# p2-001.net
KiCad netlist of a schematic drawn in EAGLE
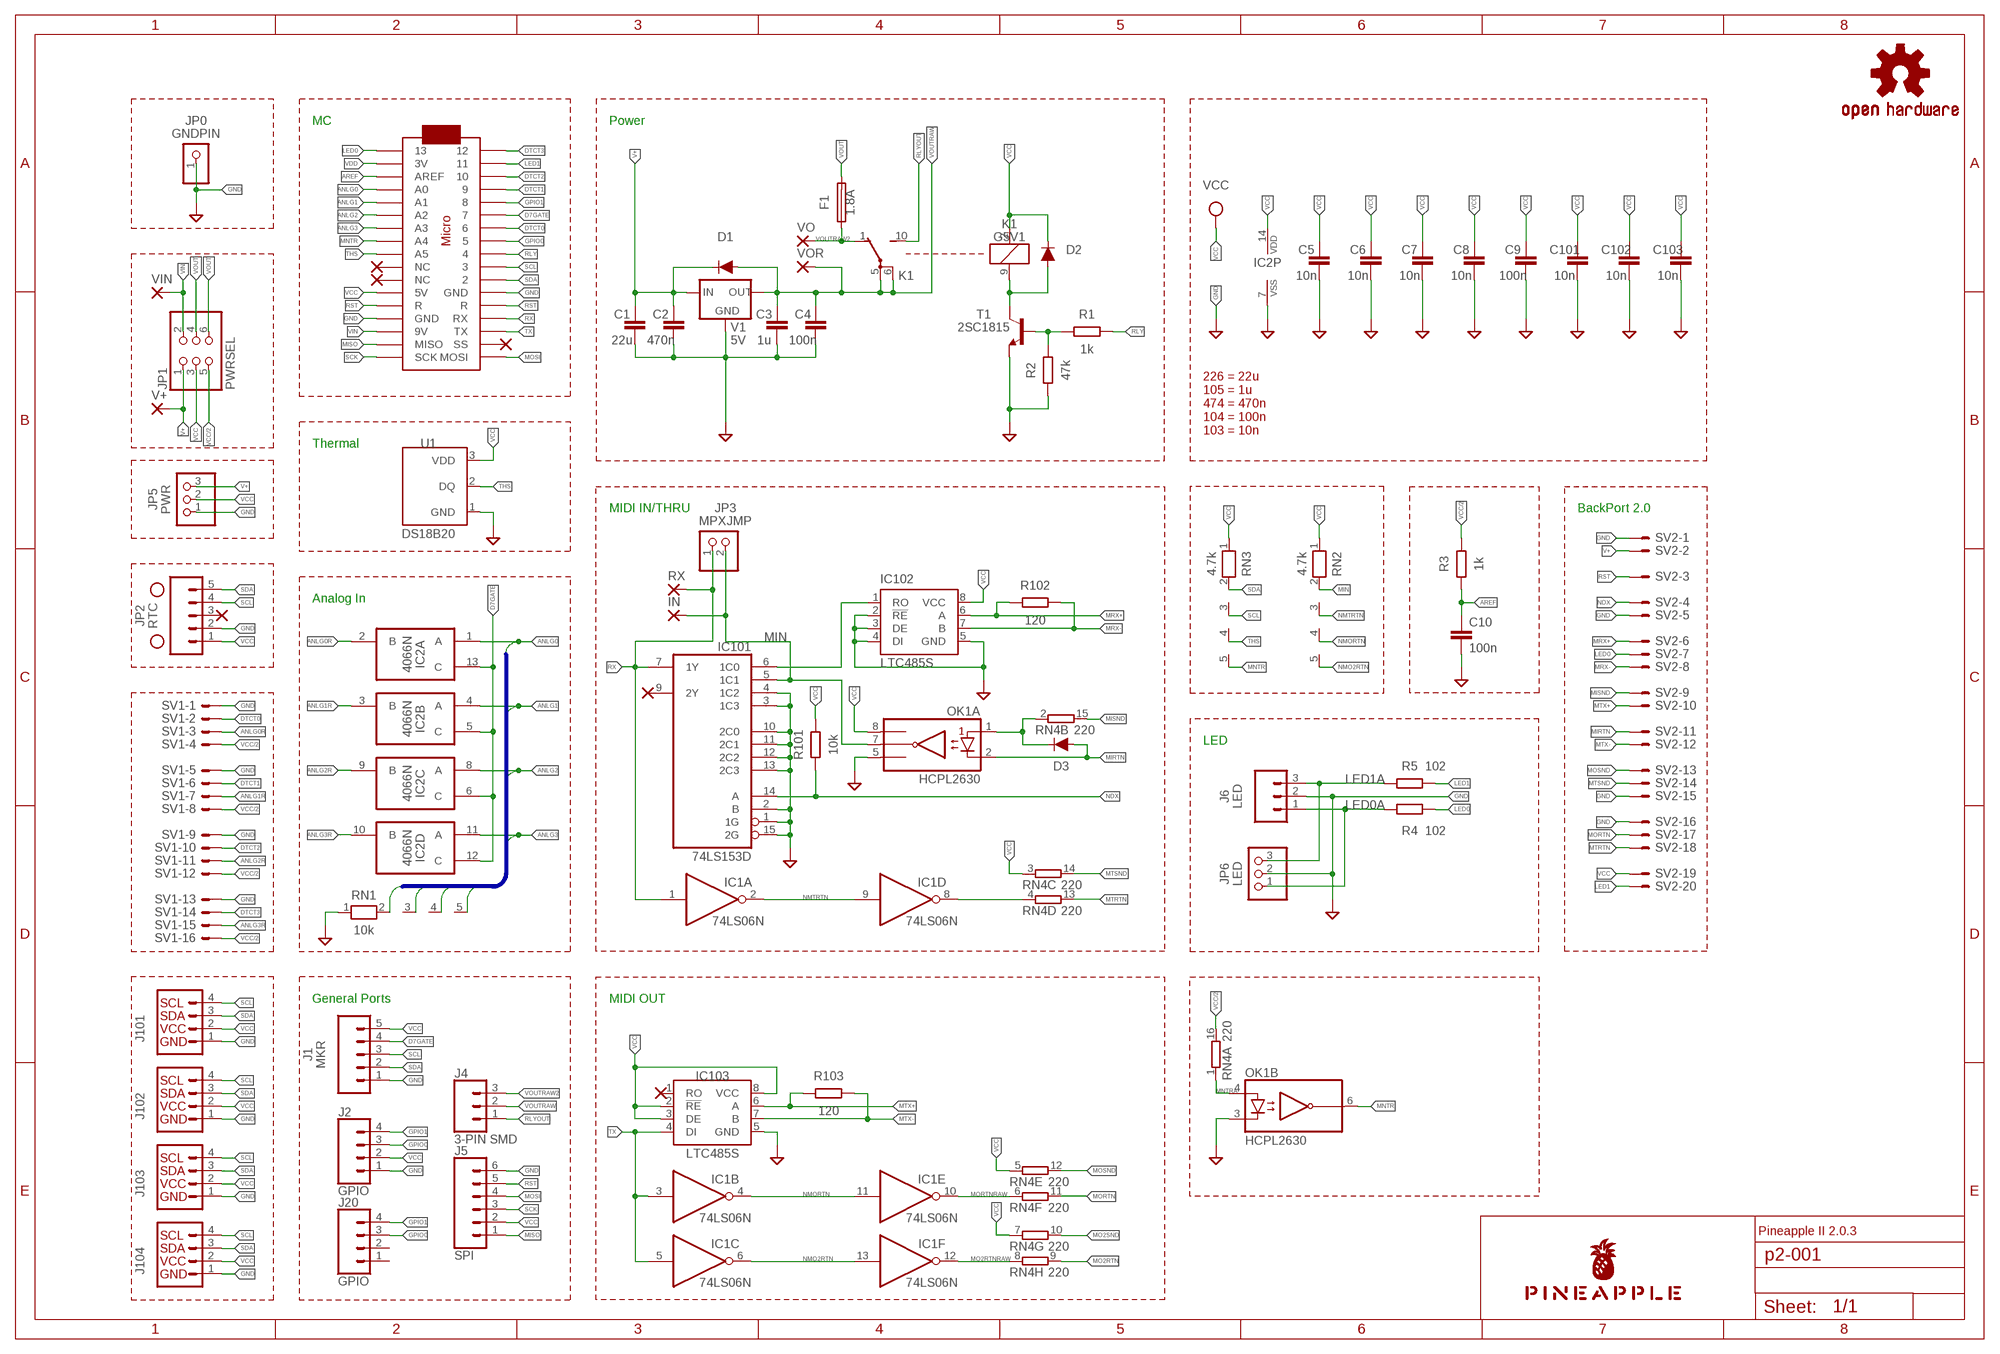
[diagram p0: schematic, sheet 1]

(export (version "E")
  (design (tool "Eeschema 10.0.6"))
  (components
    (comp (ref "C1")
      (value "22u")
      (footprint "eagle-import:C025-050X050")
      (libsource (lib "eagle-import") (part "C-EU025-050X050"))
    )
    (comp (ref "C2")
      (value "470n")
      (footprint "eagle-import:C050-024X044")
      (libsource (lib "eagle-import") (part "C-EU050-024X044"))
    )
    (comp (ref "C3")
      (value "1u")
      (footprint "eagle-import:C050-024X044")
      (libsource (lib "eagle-import") (part "C-EU050-024X044"))
    )
    (comp (ref "C4")
      (value "100n")
      (footprint "eagle-import:C025-024X044")
      (libsource (lib "eagle-import") (part "C-EU025-024X044"))
    )
    (comp (ref "C5")
      (value "10n")
      (footprint "eagle-import:C025-024X044")
      (libsource (lib "eagle-import") (part "resistor_348_C-EU025-024X044"))
    )
    (comp (ref "C6")
      (value "10n")
      (footprint "eagle-import:C025-024X044")
      (libsource (lib "eagle-import") (part "resistor_348_C-EU025-024X044"))
    )
    (comp (ref "C7")
      (value "10n")
      (footprint "eagle-import:C025-024X044")
      (libsource (lib "eagle-import") (part "resistor_348_C-EU025-024X044"))
    )
    (comp (ref "C8")
      (value "10n")
      (footprint "eagle-import:C025-024X044")
      (libsource (lib "eagle-import") (part "resistor_348_C-EU025-024X044"))
    )
    (comp (ref "C9")
      (value "100n")
      (footprint "eagle-import:C025-024X044")
      (libsource (lib "eagle-import") (part "C-EU025-024X044"))
    )
    (comp (ref "C10")
      (value "100n")
      (footprint "eagle-import:C025-024X044")
      (libsource (lib "eagle-import") (part "C-EU025-024X044"))
    )
    (comp (ref "C101")
      (value "10n")
      (footprint "eagle-import:C2012")
      (libsource (lib "eagle-import") (part "C-EUC2012"))
    )
    (comp (ref "C102")
      (value "10n")
      (footprint "eagle-import:C2012")
      (libsource (lib "eagle-import") (part "C-EUC2012"))
    )
    (comp (ref "C103")
      (value "10n")
      (footprint "eagle-import:C2012")
      (libsource (lib "eagle-import") (part "C-EUC2012"))
    )
    (comp (ref "D1")
      (value "DIODE-1N4148")
      (footprint "eagle-import:DIODE-1N4148")
      (libsource (lib "eagle-import") (part "DIODE-1N4148"))
    )
    (comp (ref "D2")
      (value "DIODE-1N4148")
      (footprint "eagle-import:DIODE-1N4148")
      (libsource (lib "eagle-import") (part "DIODE-1N4148"))
    )
    (comp (ref "D3")
      (value "DIODE-1N4148")
      (footprint "eagle-import:DIODE-1N4148")
      (libsource (lib "eagle-import") (part "DIODE-1N4148"))
    )
    (comp (ref "F1")
      (value "1.8A")
      (footprint "eagle-import:TE5")
      (libsource (lib "eagle-import") (part "TE5"))
    )
    (comp (ref "H1")
      (value "STAND-OFF")
      (footprint "eagle-import:STAND-OFF")
      (libsource (lib "eagle-import") (part "STAND-OFF"))
    )
    (comp (ref "H2")
      (value "STAND-OFF")
      (footprint "eagle-import:STAND-OFF")
      (libsource (lib "eagle-import") (part "STAND-OFF"))
    )
    (comp (ref "IC1")
      (value "74LS06N")
      (footprint "eagle-import:DIL14")
      (libsource (lib "eagle-import") (part "7406NLS"))
    )
    (comp (ref "IC2")
      (value "4066N")
      (footprint "eagle-import:DIL14")
      (libsource (lib "eagle-import") (part "4066N"))
    )
    (comp (ref "IC101")
      (value "74LS153D")
      (footprint "eagle-import:SO16")
      (libsource (lib "eagle-import") (part "74153DLS"))
    )
    (comp (ref "IC102")
      (value "LTC485S")
      (footprint "eagle-import:SOIC8")
      (libsource (lib "eagle-import") (part "LTC485S"))
    )
    (comp (ref "IC103")
      (value "LTC485S")
      (footprint "eagle-import:SOIC8")
      (libsource (lib "eagle-import") (part "LTC485S"))
    )
    (comp (ref "IN")
      (value "SMD2")
      (footprint "eagle-import:SMD1,27-2,54")
      (libsource (lib "eagle-import") (part "SMD2"))
    )
    (comp (ref "J1")
      (value "MKR")
      (footprint "eagle-import:JST-5-PTH")
      (libsource (lib "eagle-import") (part "CONN_05JST"))
    )
    (comp (ref "J2")
      (value "GPIO")
      (footprint "eagle-import:JST-4-PTH")
      (libsource (lib "eagle-import") (part "CONN_04JST-PTH"))
    )
    (comp (ref "J4")
      (value "3-PIN SMD")
      (footprint "eagle-import:JST-3-SMD")
      (libsource (lib "eagle-import") (part "SparkFun-Connectors_513_CONN_03JST-SMD"))
    )
    (comp (ref "J5")
      (value "SPI")
      (footprint "eagle-import:1X06_1.27MM")
      (libsource (lib "eagle-import") (part "CONN_061.27MM"))
    )
    (comp (ref "J6")
      (value "LED")
      (footprint "eagle-import:JST-3-PTH")
      (libsource (lib "eagle-import") (part "CONN_03JST-PTH"))
    )
    (comp (ref "J20")
      (value "GPIO")
      (footprint "eagle-import:1X04_1.27MM")
      (libsource (lib "eagle-import") (part "CONN_041.27MM"))
    )
    (comp (ref "J101")
      (value "Qwiic")
      (footprint "eagle-import:1X04_1MM_RA")
      (libsource (lib "eagle-import") (part "QWIIC_CONNECTORJS-1MM"))
    )
    (comp (ref "J102")
      (value "Qwiic")
      (footprint "eagle-import:1X04_1MM_RA")
      (libsource (lib "eagle-import") (part "QWIIC_CONNECTORJS-1MM"))
    )
    (comp (ref "J103")
      (value "Qwiic")
      (footprint "eagle-import:1X04_1MM_RA")
      (libsource (lib "eagle-import") (part "QWIIC_CONNECTORJS-1MM"))
    )
    (comp (ref "J104")
      (value "Qwiic")
      (footprint "eagle-import:1X04_1MM_RA")
      (libsource (lib "eagle-import") (part "QWIIC_CONNECTORJS-1MM"))
    )
    (comp (ref "JP0")
      (value "GNDPIN")
      (footprint "eagle-import:1X01")
      (libsource (lib "eagle-import") (part "PINHD-1X1"))
    )
    (comp (ref "JP1")
      (value "PWRSEL")
      (footprint "eagle-import:2X03")
      (libsource (lib "eagle-import") (part "PINHD-2X3"))
    )
    (comp (ref "JP2")
      (value "RTC")
      (footprint "eagle-import:1X05")
      (libsource (lib "eagle-import") (part "CONN_05"))
    )
    (comp (ref "JP3")
      (value "MPXJMP")
      (footprint "eagle-import:1X02")
      (libsource (lib "eagle-import") (part "PINHD-1X2"))
    )
    (comp (ref "JP5")
      (value "PWR")
      (footprint "eagle-import:1X03")
      (libsource (lib "eagle-import") (part "PINHD-1X3"))
    )
    (comp (ref "JP6")
      (value "LED")
      (footprint "eagle-import:1X03")
      (libsource (lib "eagle-import") (part "PINHD-1X3"))
    )
    (comp (ref "K1")
      (value "G5V1")
      (footprint "eagle-import:G5V1")
      (fields (field (name "MPN") "G5V-1-DC24"))
      (libsource (lib "eagle-import") (part "G5V1"))
    )
    (comp (ref "LOGO1")
      (value "OSHW-LOGOS-COPPER")
      (footprint "eagle-import:OSHW-LOGO-S_COPPER")
      (libsource (lib "eagle-import") (part "OSHW-LOGOS-COPPER"))
    )
    (comp (ref "MC1")
      (value "ARDUINOMICRO")
      (footprint "eagle-import:ARDUINOMICRO")
      (libsource (lib "eagle-import") (part "ARDUINOMICRO"))
    )
    (comp (ref "OK1")
      (value "HCPL2630")
      (footprint "eagle-import:DIL08")
      (fields (field (name "MF") "AGILENT TECHNOLOGIES") (field (name "MPN") "HCPL-2630-000E"))
      (libsource (lib "eagle-import") (part "HCPL2630"))
    )
    (comp (ref "R1")
      (value "1k")
      (footprint "eagle-import:0204_5")
      (libsource (lib "eagle-import") (part "resistor_348_R-EU_0204/5"))
    )
    (comp (ref "R2")
      (value "47k")
      (footprint "eagle-import:0204_5")
      (libsource (lib "eagle-import") (part "resistor_348_R-EU_0204/5"))
    )
    (comp (ref "R3")
      (value "1k")
      (footprint "eagle-import:0204_5")
      (libsource (lib "eagle-import") (part "resistor_348_R-EU_0204/5"))
    )
    (comp (ref "R4")
      (value "102")
      (footprint "eagle-import:0204_5")
      (libsource (lib "eagle-import") (part "resistor_348_R-EU_0204/5"))
    )
    (comp (ref "R5")
      (value "102")
      (footprint "eagle-import:0204_5")
      (libsource (lib "eagle-import") (part "resistor_348_R-EU_0204/5"))
    )
    (comp (ref "R101")
      (value "10k")
      (footprint "eagle-import:M2012")
      (libsource (lib "eagle-import") (part "R-EU_M2012"))
    )
    (comp (ref "R102")
      (value "120")
      (footprint "eagle-import:M2012")
      (libsource (lib "eagle-import") (part "R-EU_M2012"))
    )
    (comp (ref "R103")
      (value "120")
      (footprint "eagle-import:M2012")
      (libsource (lib "eagle-import") (part "R-EU_M2012"))
    )
    (comp (ref "RN1")
      (value "10k")
      (footprint "eagle-import:RN-5")
      (libsource (lib "eagle-import") (part "RN04"))
    )
    (comp (ref "RN2")
      (value "4.7k")
      (footprint "eagle-import:RN-5")
      (libsource (lib "eagle-import") (part "RN04"))
    )
    (comp (ref "RN3")
      (value "4.7k")
      (footprint "eagle-import:RN-5")
      (libsource (lib "eagle-import") (part "RN04"))
    )
    (comp (ref "RN4")
      (value "220")
      (footprint "eagle-import:DIL16")
      (libsource (lib "eagle-import") (part "8R-N"))
    )
    (comp (ref "RX")
      (value "SMD2")
      (footprint "eagle-import:SMD1,27-2,54")
      (libsource (lib "eagle-import") (part "SMD2"))
    )
    (comp (ref "SV1")
      (value "ML16LE")
      (footprint "eagle-import:ML16L")
      (libsource (lib "eagle-import") (part "ML16LE"))
    )
    (comp (ref "SV2")
      (value "ML20LE")
      (footprint "eagle-import:ML20L")
      (libsource (lib "eagle-import") (part "ML20LE"))
    )
    (comp (ref "T1")
      (value "2SC1815")
      (footprint "eagle-import:TO92-ECB")
      (libsource (lib "eagle-import") (part "2SC1815"))
    )
    (comp (ref "U$1")
      (value "PINEAPPLE450_SILK")
      (footprint "eagle-import:PINEAPPLE450_SILK")
      (libsource (lib "eagle-import") (part "PINEAPPLE450_SILK"))
    )
    (comp (ref "U1")
      (value "DS18B20")
      (footprint "eagle-import:TO-92-AMMO")
      (libsource (lib "eagle-import") (part "DS18B20"))
    )
    (comp (ref "V+")
      (value "SMD2")
      (footprint "eagle-import:SMD1,27-2,54")
      (libsource (lib "eagle-import") (part "SMD2"))
    )
    (comp (ref "V1")
      (value "5V")
      (footprint "eagle-import:78XXL")
      (libsource (lib "eagle-import") (part "78XXL"))
    )
    (comp (ref "VIN")
      (value "SMD2")
      (footprint "eagle-import:SMD1,27-2,54")
      (libsource (lib "eagle-import") (part "SMD2"))
    )
    (comp (ref "VO")
      (value "SMD2")
      (footprint "eagle-import:SMD1,27-2,54")
      (libsource (lib "eagle-import") (part "SMD2"))
    )
    (comp (ref "VOR")
      (value "SMD2")
      (footprint "eagle-import:SMD1,27-2,54")
      (libsource (lib "eagle-import") (part "SMD2"))
    )
  )
  (nets
    (net (code "1") (name "/LED0A") (class "Default")
      (node (ref "J6") (pin "1") (pinfunction "1_1") (pintype "passive"))
      (node (ref "JP6") (pin "1") (pinfunction "1_1") (pintype "passive"))
      (node (ref "R4") (pin "1") (pinfunction "1_1") (pintype "passive"))
    )
    (net (code "2") (name "/LED1A") (class "Default")
      (node (ref "J6") (pin "3") (pinfunction "3_3") (pintype "passive"))
      (node (ref "JP6") (pin "3") (pinfunction "3_3") (pintype "passive"))
      (node (ref "R5") (pin "1") (pinfunction "1_1") (pintype "passive"))
    )
    (net (code "3") (name "/MNTRA") (class "Default")
      (node (ref "OK1") (pin "4") (pinfunction "A2_4") (pintype "passive"))
      (node (ref "RN4") (pin "1") (pinfunction "1_1") (pintype "passive"))
    )
    (net (code "4") (name "/MO2RTNRAW") (class "Default")
      (node (ref "IC1") (pin "12") (pinfunction "O_12") (pintype "open_collector"))
      (node (ref "RN4") (pin "8") (pinfunction "1_8") (pintype "passive"))
    )
    (net (code "5") (name "/MORTNRAW") (class "Default")
      (node (ref "IC1") (pin "10") (pinfunction "O_10") (pintype "open_collector"))
      (node (ref "RN4") (pin "6") (pinfunction "1_6") (pintype "passive"))
    )
    (net (code "6") (name "ANLG0") (class "Default")
      (node (ref "IC2") (pin "1") (pinfunction "A_1") (pintype "tri_state"))
      (node (ref "MC1") (pin "P$31") (pinfunction "A0_P$31") (pintype "bidirectional"))
      (node (ref "RN1") (pin "2") (pinfunction "2_2") (pintype "passive"))
    )
    (net (code "7") (name "ANLG0R") (class "Default")
      (node (ref "IC2") (pin "2") (pinfunction "B_2") (pintype "tri_state"))
      (node (ref "SV1") (pin "3") (pinfunction "S_3") (pintype "passive"))
    )
    (net (code "8") (name "ANLG1") (class "Default")
      (node (ref "IC2") (pin "4") (pinfunction "A_4") (pintype "tri_state"))
      (node (ref "MC1") (pin "P$30") (pinfunction "A1_P$30") (pintype "bidirectional"))
      (node (ref "RN1") (pin "3") (pinfunction "3_3") (pintype "passive"))
    )
    (net (code "9") (name "ANLG1R") (class "Default")
      (node (ref "IC2") (pin "3") (pinfunction "B_3") (pintype "tri_state"))
      (node (ref "SV1") (pin "7") (pinfunction "S_7") (pintype "passive"))
    )
    (net (code "10") (name "ANLG2") (class "Default")
      (node (ref "IC2") (pin "8") (pinfunction "A_8") (pintype "tri_state"))
      (node (ref "MC1") (pin "P$29") (pinfunction "A2_P$29") (pintype "bidirectional"))
      (node (ref "RN1") (pin "4") (pinfunction "4_4") (pintype "passive"))
    )
    (net (code "11") (name "ANLG2R") (class "Default")
      (node (ref "IC2") (pin "9") (pinfunction "B_9") (pintype "tri_state"))
      (node (ref "SV1") (pin "11") (pinfunction "S_11") (pintype "passive"))
    )
    (net (code "12") (name "ANLG3") (class "Default")
      (node (ref "IC2") (pin "11") (pinfunction "A_11") (pintype "tri_state"))
      (node (ref "MC1") (pin "P$28") (pinfunction "A3_P$28") (pintype "bidirectional"))
      (node (ref "RN1") (pin "5") (pinfunction "5_5") (pintype "passive"))
    )
    (net (code "13") (name "ANLG3R") (class "Default")
      (node (ref "IC2") (pin "10") (pinfunction "B_10") (pintype "tri_state"))
      (node (ref "SV1") (pin "15") (pinfunction "S_15") (pintype "passive"))
    )
    (net (code "14") (name "AREF") (class "Default")
      (node (ref "C10") (pin "1") (pinfunction "1_1") (pintype "passive"))
      (node (ref "MC1") (pin "P$32") (pinfunction "AREF_P$32") (pintype "bidirectional"))
      (node (ref "R3") (pin "1") (pinfunction "1_1") (pintype "passive"))
    )
    (net (code "15") (name "D7GATE") (class "Default")
      (node (ref "IC2") (pin "12") (pinfunction "C_12") (pintype "input"))
      (node (ref "IC2") (pin "13") (pinfunction "C_13") (pintype "input"))
      (node (ref "IC2") (pin "5") (pinfunction "C_5") (pintype "input"))
      (node (ref "IC2") (pin "6") (pinfunction "C_6") (pintype "input"))
      (node (ref "J1") (pin "4") (pinfunction "4_4") (pintype "passive"))
      (node (ref "MC1") (pin "P$6") (pinfunction "7_P$6") (pintype "bidirectional"))
    )
    (net (code "16") (name "DTCT0") (class "Default")
      (node (ref "MC1") (pin "P$7") (pinfunction "6_P$7") (pintype "bidirectional"))
      (node (ref "SV1") (pin "2") (pinfunction "S_2") (pintype "passive"))
    )
    (net (code "17") (name "DTCT1") (class "Default")
      (node (ref "MC1") (pin "P$4") (pinfunction "9_P$4") (pintype "bidirectional"))
      (node (ref "SV1") (pin "6") (pinfunction "S_6") (pintype "passive"))
    )
    (net (code "18") (name "DTCT2") (class "Default")
      (node (ref "MC1") (pin "P$3") (pinfunction "10_P$3") (pintype "bidirectional"))
      (node (ref "SV1") (pin "10") (pinfunction "S_10") (pintype "passive"))
    )
    (net (code "19") (name "DTCT3") (class "Default")
      (node (ref "MC1") (pin "P$1") (pinfunction "12_P$1") (pintype "bidirectional"))
      (node (ref "SV1") (pin "14") (pinfunction "S_14") (pintype "passive"))
    )
    (net (code "20") (name "GND") (class "Default")
      (node (ref "C1") (pin "2") (pinfunction "2_2") (pintype "passive"))
      (node (ref "C10") (pin "2") (pinfunction "2_2") (pintype "passive"))
      (node (ref "C101") (pin "2") (pinfunction "2_2") (pintype "passive"))
      (node (ref "C102") (pin "2") (pinfunction "2_2") (pintype "passive"))
      (node (ref "C103") (pin "2") (pinfunction "2_2") (pintype "passive"))
      (node (ref "C2") (pin "2") (pinfunction "2_2") (pintype "passive"))
      (node (ref "C3") (pin "2") (pinfunction "2_2") (pintype "passive"))
      (node (ref "C4") (pin "2") (pinfunction "2_2") (pintype "passive"))
      (node (ref "C5") (pin "2") (pinfunction "2_2") (pintype "passive"))
      (node (ref "C6") (pin "2") (pinfunction "2_2") (pintype "passive"))
      (node (ref "C7") (pin "2") (pinfunction "2_2") (pintype "passive"))
      (node (ref "C8") (pin "2") (pinfunction "2_2") (pintype "passive"))
      (node (ref "C9") (pin "2") (pinfunction "2_2") (pintype "passive"))
      (node (ref "IC101") (pin "1") (pinfunction "1G_1") (pintype "input"))
      (node (ref "IC101") (pin "10") (pinfunction "2C0_10") (pintype "input"))
      (node (ref "IC101") (pin "11") (pinfunction "2C1_11") (pintype "input"))
      (node (ref "IC101") (pin "12") (pinfunction "2C2_12") (pintype "input"))
      (node (ref "IC101") (pin "13") (pinfunction "2C3_13") (pintype "input"))
      (node (ref "IC101") (pin "15") (pinfunction "2G_15") (pintype "input"))
      (node (ref "IC101") (pin "2") (pinfunction "B_2") (pintype "input"))
      (node (ref "IC101") (pin "3") (pinfunction "1C3_3") (pintype "input"))
      (node (ref "IC101") (pin "4") (pinfunction "1C2_4") (pintype "input"))
      (node (ref "IC102") (pin "2") (pinfunction "~{RE}_2") (pintype "input"))
      (node (ref "IC102") (pin "3") (pinfunction "DE_3") (pintype "input"))
      (node (ref "IC102") (pin "4") (pinfunction "DI_4") (pintype "input"))
      (node (ref "IC102") (pin "5") (pinfunction "GND_5") (pintype "input"))
      (node (ref "IC103") (pin "5") (pinfunction "GND_5") (pintype "input"))
      (node (ref "IC2") (pin "7") (pinfunction "VSS_7") (pintype "power_in"))
      (node (ref "J1") (pin "1") (pinfunction "1_1") (pintype "passive"))
      (node (ref "J101") (pin "1") (pinfunction "GND_1") (pintype "power_in"))
      (node (ref "J102") (pin "1") (pinfunction "GND_1") (pintype "power_in"))
      (node (ref "J103") (pin "1") (pinfunction "GND_1") (pintype "power_in"))
      (node (ref "J104") (pin "1") (pinfunction "GND_1") (pintype "power_in"))
      (node (ref "J2") (pin "1") (pinfunction "1_1") (pintype "passive"))
      (node (ref "J5") (pin "6") (pinfunction "6_6") (pintype "passive"))
      (node (ref "J6") (pin "2") (pinfunction "2_2") (pintype "passive"))
      (node (ref "JP0") (pin "1") (pinfunction "1_1") (pintype "passive"))
      (node (ref "JP2") (pin "2") (pinfunction "2_2") (pintype "passive"))
      (node (ref "JP5") (pin "1") (pinfunction "1_1") (pintype "passive"))
      (node (ref "JP6") (pin "2") (pinfunction "2_2") (pintype "passive"))
      (node (ref "MC1") (pin "P$12") (pinfunction "GND_P$12") (pintype "bidirectional"))
      (node (ref "MC1") (pin "P$21") (pinfunction "GND_P$21") (pintype "bidirectional"))
      (node (ref "OK1") (pin "3") (pinfunction "C2_3") (pintype "passive"))
      (node (ref "OK1") (pin "5") (pinfunction "GND_5") (pintype "passive"))
      (node (ref "R2") (pin "1") (pinfunction "1_1") (pintype "passive"))
      (node (ref "RN1") (pin "1") (pinfunction "1_1") (pintype "passive"))
      (node (ref "SV1") (pin "1") (pinfunction "S_1") (pintype "passive"))
      (node (ref "SV1") (pin "13") (pinfunction "S_13") (pintype "passive"))
      (node (ref "SV1") (pin "5") (pinfunction "S_5") (pintype "passive"))
      (node (ref "SV1") (pin "9") (pinfunction "S_9") (pintype "passive"))
      (node (ref "SV2") (pin "1") (pinfunction "S_1") (pintype "passive"))
      (node (ref "SV2") (pin "15") (pinfunction "S_15") (pintype "passive"))
      (node (ref "SV2") (pin "16") (pinfunction "S_16") (pintype "passive"))
      (node (ref "SV2") (pin "5") (pinfunction "S_5") (pintype "passive"))
      (node (ref "T1") (pin "E") (pinfunction "E_E") (pintype "passive"))
      (node (ref "U1") (pin "1") (pinfunction "GND_1") (pintype "power_in"))
      (node (ref "V1") (pin "GND") (pinfunction "GND_GND") (pintype "input"))
    )
    (net (code "21") (name "GPIO0") (class "Default")
      (node (ref "J2") (pin "3") (pinfunction "3_3") (pintype "passive"))
      (node (ref "J20") (pin "3") (pinfunction "3_3") (pintype "passive"))
      (node (ref "MC1") (pin "P$8") (pinfunction "5_P$8") (pintype "bidirectional"))
    )
    (net (code "22") (name "GPIO1") (class "Default")
      (node (ref "J2") (pin "4") (pinfunction "4_4") (pintype "passive"))
      (node (ref "J20") (pin "4") (pinfunction "4_4") (pintype "passive"))
      (node (ref "MC1") (pin "P$5") (pinfunction "8_P$5") (pintype "bidirectional"))
    )
    (net (code "23") (name "LED0") (class "Default")
      (node (ref "MC1") (pin "P$34") (pinfunction "13_P$34") (pintype "bidirectional"))
      (node (ref "R4") (pin "2") (pinfunction "2_2") (pintype "passive"))
      (node (ref "SV2") (pin "7") (pinfunction "S_7") (pintype "passive"))
    )
    (net (code "24") (name "LED1") (class "Default")
      (node (ref "MC1") (pin "P$2") (pinfunction "11_P$2") (pintype "bidirectional"))
      (node (ref "R5") (pin "2") (pinfunction "2_2") (pintype "passive"))
      (node (ref "SV2") (pin "20") (pinfunction "S_20") (pintype "passive"))
    )
    (net (code "25") (name "MIN") (class "Default")
      (node (ref "IC101") (pin "5") (pinfunction "1C1_5") (pintype "input"))
      (node (ref "IN") (pin "1") (pinfunction "P_1") (pintype "passive"))
      (node (ref "JP3") (pin "2") (pinfunction "2_2") (pintype "passive"))
      (node (ref "OK1") (pin "7") (pinfunction "VO1_7") (pintype "passive"))
      (node (ref "RN2") (pin "2") (pinfunction "2_2") (pintype "passive"))
    )
    (net (code "26") (name "MIRTN") (class "Default")
      (node (ref "D3") (pin "A") (pinfunction "A_A") (pintype "passive"))
      (node (ref "OK1") (pin "2") (pinfunction "C1_2") (pintype "passive"))
      (node (ref "SV2") (pin "11") (pinfunction "S_11") (pintype "passive"))
    )
    (net (code "27") (name "MISND") (class "Default")
      (node (ref "RN4") (pin "15") (pinfunction "2_15") (pintype "passive"))
      (node (ref "SV2") (pin "9") (pinfunction "S_9") (pintype "passive"))
    )
    (net (code "28") (name "MISO") (class "Default")
      (node (ref "J5") (pin "1") (pinfunction "1_1") (pintype "passive"))
      (node (ref "MC1") (pin "P$19") (pinfunction "MISO_P$19") (pintype "bidirectional"))
    )
    (net (code "29") (name "MNTR") (class "Default")
      (node (ref "MC1") (pin "P$27") (pinfunction "A4_P$27") (pintype "bidirectional"))
      (node (ref "OK1") (pin "6") (pinfunction "VO2_6") (pintype "passive"))
      (node (ref "RN3") (pin "5") (pinfunction "5_5") (pintype "passive"))
    )
    (net (code "30") (name "MO2RTN") (class "Default")
      (node (ref "RN4") (pin "9") (pinfunction "2_9") (pintype "passive"))
    )
    (net (code "31") (name "MO2SND") (class "Default")
      (node (ref "RN4") (pin "10") (pinfunction "2_10") (pintype "passive"))
    )
    (net (code "32") (name "MORTN") (class "Default")
      (node (ref "RN4") (pin "11") (pinfunction "2_11") (pintype "passive"))
      (node (ref "SV2") (pin "17") (pinfunction "S_17") (pintype "passive"))
    )
    (net (code "33") (name "MOSI") (class "Default")
      (node (ref "J5") (pin "4") (pinfunction "4_4") (pintype "passive"))
      (node (ref "MC1") (pin "P$17") (pinfunction "MOSI_P$17") (pintype "bidirectional"))
    )
    (net (code "34") (name "MOSND") (class "Default")
      (node (ref "RN4") (pin "12") (pinfunction "2_12") (pintype "passive"))
      (node (ref "SV2") (pin "13") (pinfunction "S_13") (pintype "passive"))
    )
    (net (code "35") (name "MRX+") (class "Default")
      (node (ref "IC102") (pin "6") (pinfunction "A_6") (pintype "bidirectional"))
      (node (ref "R102") (pin "1") (pinfunction "1_1") (pintype "passive"))
      (node (ref "SV2") (pin "6") (pinfunction "S_6") (pintype "passive"))
    )
    (net (code "36") (name "MRX-") (class "Default")
      (node (ref "IC102") (pin "7") (pinfunction "B_7") (pintype "bidirectional"))
      (node (ref "R102") (pin "2") (pinfunction "2_2") (pintype "passive"))
      (node (ref "SV2") (pin "8") (pinfunction "S_8") (pintype "passive"))
    )
    (net (code "37") (name "MTRTN") (class "Default")
      (node (ref "RN4") (pin "13") (pinfunction "2_13") (pintype "passive"))
      (node (ref "SV2") (pin "18") (pinfunction "S_18") (pintype "passive"))
    )
    (net (code "38") (name "MTSND") (class "Default")
      (node (ref "RN4") (pin "14") (pinfunction "2_14") (pintype "passive"))
      (node (ref "SV2") (pin "14") (pinfunction "S_14") (pintype "passive"))
    )
    (net (code "39") (name "MTX+") (class "Default")
      (node (ref "IC103") (pin "6") (pinfunction "A_6") (pintype "bidirectional"))
      (node (ref "R103") (pin "1") (pinfunction "1_1") (pintype "passive"))
      (node (ref "SV2") (pin "10") (pinfunction "S_10") (pintype "passive"))
    )
    (net (code "40") (name "MTX-") (class "Default")
      (node (ref "IC103") (pin "7") (pinfunction "B_7") (pintype "bidirectional"))
      (node (ref "R103") (pin "2") (pinfunction "2_2") (pintype "passive"))
      (node (ref "SV2") (pin "12") (pinfunction "S_12") (pintype "passive"))
    )
    (net (code "41") (name "NDX") (class "Default")
      (node (ref "IC101") (pin "14") (pinfunction "A_14") (pintype "input"))
      (node (ref "R101") (pin "1") (pinfunction "1_1") (pintype "passive"))
      (node (ref "SV2") (pin "4") (pinfunction "S_4") (pintype "passive"))
    )
    (net (code "42") (name "NMO2RTN") (class "Default")
      (node (ref "IC1") (pin "13") (pinfunction "I_13") (pintype "input"))
      (node (ref "IC1") (pin "6") (pinfunction "O_6") (pintype "open_collector"))
      (node (ref "RN2") (pin "5") (pinfunction "5_5") (pintype "passive"))
    )
    (net (code "43") (name "NMORTN") (class "Default")
      (node (ref "IC1") (pin "11") (pinfunction "I_11") (pintype "input"))
      (node (ref "IC1") (pin "4") (pinfunction "O_4") (pintype "open_collector"))
      (node (ref "RN2") (pin "4") (pinfunction "4_4") (pintype "passive"))
    )
    (net (code "44") (name "NMTRTN") (class "Default")
      (node (ref "IC1") (pin "2") (pinfunction "O_2") (pintype "open_collector"))
      (node (ref "IC1") (pin "9") (pinfunction "I_9") (pintype "input"))
      (node (ref "RN2") (pin "3") (pinfunction "3_3") (pintype "passive"))
    )
    (net (code "45") (name "Net-(IC1D-O)") (class "Default")
      (node (ref "IC1") (pin "8") (pinfunction "O_8") (pintype "open_collector"))
      (node (ref "RN4") (pin "4") (pinfunction "1_4") (pintype "passive"))
    )
    (net (code "46") (name "Net-(IC101A-1C0)") (class "Default")
      (node (ref "IC101") (pin "6") (pinfunction "1C0_6") (pintype "input"))
      (node (ref "IC102") (pin "1") (pinfunction "RO_1") (pintype "output"))
    )
    (net (code "47") (name "Net-(K1A-2)") (class "Default")
      (node (ref "D2") (pin "A") (pinfunction "A_A") (pintype "passive"))
      (node (ref "K1") (pin "9") (pinfunction "2_9") (pintype "passive"))
      (node (ref "T1") (pin "C") (pinfunction "C_C") (pintype "passive"))
    )
    (net (code "48") (name "Net-(OK1A-A1)") (class "Default")
      (node (ref "D3") (pin "C") (pinfunction "C_C") (pintype "passive"))
      (node (ref "OK1") (pin "1") (pinfunction "A1_1") (pintype "passive"))
      (node (ref "RN4") (pin "2") (pinfunction "1_2") (pintype "passive"))
    )
    (net (code "49") (name "Net-(R1-Pad1)") (class "Default")
      (node (ref "R1") (pin "1") (pinfunction "1_1") (pintype "passive"))
      (node (ref "R2") (pin "2") (pinfunction "2_2") (pintype "passive"))
      (node (ref "T1") (pin "B") (pinfunction "B_B") (pintype "passive"))
    )
    (net (code "50") (name "RLY") (class "Default")
      (node (ref "MC1") (pin "P$9") (pinfunction "4_P$9") (pintype "bidirectional"))
      (node (ref "R1") (pin "2") (pinfunction "2_2") (pintype "passive"))
    )
    (net (code "51") (name "RLYOUT") (class "Default")
      (node (ref "J4") (pin "1") (pinfunction "1_1") (pintype "passive"))
      (node (ref "K1") (pin "10") (pinfunction "S_10") (pintype "passive"))
    )
    (net (code "52") (name "RST") (class "Default")
      (node (ref "J5") (pin "5") (pinfunction "5_5") (pintype "passive"))
      (node (ref "MC1") (pin "P$13") (pinfunction "R_P$13") (pintype "bidirectional"))
      (node (ref "MC1") (pin "P$22") (pinfunction "R_P$22") (pintype "bidirectional"))
      (node (ref "SV2") (pin "3") (pinfunction "S_3") (pintype "passive"))
    )
    (net (code "53") (name "RX") (class "Default")
      (node (ref "IC1") (pin "1") (pinfunction "I_1") (pintype "input"))
      (node (ref "IC101") (pin "7") (pinfunction "1Y_7") (pintype "output"))
      (node (ref "JP3") (pin "1") (pinfunction "1_1") (pintype "passive"))
      (node (ref "MC1") (pin "P$14") (pinfunction "RX_P$14") (pintype "bidirectional"))
      (node (ref "RX") (pin "1") (pinfunction "P_1") (pintype "passive"))
    )
    (net (code "54") (name "SCK") (class "Default")
      (node (ref "J5") (pin "3") (pinfunction "3_3") (pintype "passive"))
      (node (ref "MC1") (pin "P$18") (pinfunction "SCK_P$18") (pintype "bidirectional"))
    )
    (net (code "55") (name "SCL") (class "Default")
      (node (ref "J1") (pin "3") (pinfunction "3_3") (pintype "passive"))
      (node (ref "J101") (pin "4") (pinfunction "SCL_4") (pintype "passive"))
      (node (ref "J102") (pin "4") (pinfunction "SCL_4") (pintype "passive"))
      (node (ref "J103") (pin "4") (pinfunction "SCL_4") (pintype "passive"))
      (node (ref "J104") (pin "4") (pinfunction "SCL_4") (pintype "passive"))
      (node (ref "JP2") (pin "4") (pinfunction "4_4") (pintype "passive"))
      (node (ref "MC1") (pin "P$10") (pinfunction "3_P$10") (pintype "bidirectional"))
      (node (ref "RN3") (pin "3") (pinfunction "3_3") (pintype "passive"))
    )
    (net (code "56") (name "SDA") (class "Default")
      (node (ref "J1") (pin "2") (pinfunction "2_2") (pintype "passive"))
      (node (ref "J101") (pin "3") (pinfunction "SDA_3") (pintype "passive"))
      (node (ref "J102") (pin "3") (pinfunction "SDA_3") (pintype "passive"))
      (node (ref "J103") (pin "3") (pinfunction "SDA_3") (pintype "passive"))
      (node (ref "J104") (pin "3") (pinfunction "SDA_3") (pintype "passive"))
      (node (ref "JP2") (pin "5") (pinfunction "5_5") (pintype "passive"))
      (node (ref "MC1") (pin "P$11") (pinfunction "2_P$11") (pintype "bidirectional"))
      (node (ref "RN3") (pin "2") (pinfunction "2_2") (pintype "passive"))
    )
    (net (code "57") (name "THS") (class "Default")
      (node (ref "MC1") (pin "P$26") (pinfunction "A5_P$26") (pintype "bidirectional"))
      (node (ref "RN3") (pin "4") (pinfunction "4_4") (pintype "passive"))
      (node (ref "U1") (pin "2") (pinfunction "DQ_2") (pintype "bidirectional"))
    )
    (net (code "58") (name "TX") (class "Default")
      (node (ref "IC1") (pin "3") (pinfunction "I_3") (pintype "input"))
      (node (ref "IC1") (pin "5") (pinfunction "I_5") (pintype "input"))
      (node (ref "IC103") (pin "4") (pinfunction "DI_4") (pintype "input"))
      (node (ref "MC1") (pin "P$15") (pinfunction "TX_P$15") (pintype "bidirectional"))
    )
    (net (code "59") (name "V+") (class "Default")
      (node (ref "C1") (pin "1") (pinfunction "1_1") (pintype "passive"))
      (node (ref "C2") (pin "1") (pinfunction "1_1") (pintype "passive"))
      (node (ref "D1") (pin "C") (pinfunction "C_C") (pintype "passive"))
      (node (ref "JP1") (pin "1") (pinfunction "1_1") (pintype "passive"))
      (node (ref "JP5") (pin "3") (pinfunction "3_3") (pintype "passive"))
      (node (ref "SV2") (pin "2") (pinfunction "S_2") (pintype "passive"))
      (node (ref "V+") (pin "1") (pinfunction "P_1") (pintype "passive"))
      (node (ref "V1") (pin "IN") (pinfunction "IN_IN") (pintype "input"))
    )
    (net (code "60") (name "VCC") (class "Default")
      (node (ref "C101") (pin "1") (pinfunction "1_1") (pintype "passive"))
      (node (ref "C102") (pin "1") (pinfunction "1_1") (pintype "passive"))
      (node (ref "C103") (pin "1") (pinfunction "1_1") (pintype "passive"))
      (node (ref "C5") (pin "1") (pinfunction "1_1") (pintype "passive"))
      (node (ref "C6") (pin "1") (pinfunction "1_1") (pintype "passive"))
      (node (ref "C7") (pin "1") (pinfunction "1_1") (pintype "passive"))
      (node (ref "C8") (pin "1") (pinfunction "1_1") (pintype "passive"))
      (node (ref "C9") (pin "1") (pinfunction "1_1") (pintype "passive"))
      (node (ref "D2") (pin "C") (pinfunction "C_C") (pintype "passive"))
      (node (ref "IC102") (pin "8") (pinfunction "VCC_8") (pintype "input"))
      (node (ref "IC103") (pin "2") (pinfunction "~{RE}_2") (pintype "input"))
      (node (ref "IC103") (pin "3") (pinfunction "DE_3") (pintype "input"))
      (node (ref "IC103") (pin "8") (pinfunction "VCC_8") (pintype "input"))
      (node (ref "IC2") (pin "14") (pinfunction "VDD_14") (pintype "power_in"))
      (node (ref "J1") (pin "5") (pinfunction "5_5") (pintype "passive"))
      (node (ref "J101") (pin "2") (pinfunction "VCC_2") (pintype "power_in"))
      (node (ref "J102") (pin "2") (pinfunction "VCC_2") (pintype "power_in"))
      (node (ref "J103") (pin "2") (pinfunction "VCC_2") (pintype "power_in"))
      (node (ref "J104") (pin "2") (pinfunction "VCC_2") (pintype "power_in"))
      (node (ref "J2") (pin "2") (pinfunction "2_2") (pintype "passive"))
      (node (ref "J5") (pin "2") (pinfunction "2_2") (pintype "passive"))
      (node (ref "JP1") (pin "3") (pinfunction "3_3") (pintype "passive"))
      (node (ref "JP2") (pin "1") (pinfunction "1_1") (pintype "passive"))
      (node (ref "JP5") (pin "2") (pinfunction "2_2") (pintype "passive"))
      (node (ref "K1") (pin "2") (pinfunction "1_2") (pintype "passive"))
      (node (ref "MC1") (pin "P$23") (pinfunction "5V_P$23") (pintype "bidirectional"))
      (node (ref "OK1") (pin "8") (pinfunction "VCC_8") (pintype "passive"))
      (node (ref "R101") (pin "2") (pinfunction "2_2") (pintype "passive"))
      (node (ref "RN2") (pin "1") (pinfunction "1_1") (pintype "passive"))
      (node (ref "RN3") (pin "1") (pinfunction "1_1") (pintype "passive"))
      (node (ref "RN4") (pin "3") (pinfunction "1_3") (pintype "passive"))
      (node (ref "RN4") (pin "5") (pinfunction "1_5") (pintype "passive"))
      (node (ref "RN4") (pin "7") (pinfunction "1_7") (pintype "passive"))
      (node (ref "SV2") (pin "19") (pinfunction "S_19") (pintype "passive"))
      (node (ref "U1") (pin "3") (pinfunction "VDD_3") (pintype "power_in"))
    )
    (net (code "61") (name "VCC{slash}2") (class "Default")
      (node (ref "JP1") (pin "5") (pinfunction "5_5") (pintype "passive"))
      (node (ref "R3") (pin "2") (pinfunction "2_2") (pintype "passive"))
      (node (ref "RN4") (pin "16") (pinfunction "2_16") (pintype "passive"))
      (node (ref "SV1") (pin "12") (pinfunction "S_12") (pintype "passive"))
      (node (ref "SV1") (pin "16") (pinfunction "S_16") (pintype "passive"))
      (node (ref "SV1") (pin "4") (pinfunction "S_4") (pintype "passive"))
      (node (ref "SV1") (pin "8") (pinfunction "S_8") (pintype "passive"))
    )
    (net (code "62") (name "VDD") (class "Default")
      (node (ref "MC1") (pin "P$33") (pinfunction "3V_P$33") (pintype "bidirectional"))
    )
    (net (code "63") (name "VIN") (class "Default")
      (node (ref "JP1") (pin "2") (pinfunction "2_2") (pintype "passive"))
      (node (ref "MC1") (pin "P$20") (pinfunction "9V_P$20") (pintype "bidirectional"))
      (node (ref "VIN") (pin "1") (pinfunction "P_1") (pintype "passive"))
    )
    (net (code "64") (name "VOUT") (class "Default")
      (node (ref "F1") (pin "2") (pinfunction "2_2") (pintype "passive"))
      (node (ref "JP1") (pin "4") (pinfunction "4_4") (pintype "passive"))
      (node (ref "JP1") (pin "6") (pinfunction "6_6") (pintype "passive"))
    )
    (net (code "65") (name "VOUTRAW") (class "Default")
      (node (ref "C3") (pin "1") (pinfunction "1_1") (pintype "passive"))
      (node (ref "C4") (pin "1") (pinfunction "1_1") (pintype "passive"))
      (node (ref "D1") (pin "A") (pinfunction "A_A") (pintype "passive"))
      (node (ref "J4") (pin "2") (pinfunction "2_2") (pintype "passive"))
      (node (ref "K1") (pin "5") (pinfunction "P_5") (pintype "passive"))
      (node (ref "K1") (pin "6") (pinfunction "P_6") (pintype "passive"))
      (node (ref "V1") (pin "OUT") (pinfunction "OUT_OUT") (pintype "passive"))
      (node (ref "VOR") (pin "1") (pinfunction "P_1") (pintype "passive"))
    )
    (net (code "66") (name "VOUTRAW2") (class "Default")
      (node (ref "F1") (pin "1") (pinfunction "1_1") (pintype "passive"))
      (node (ref "J4") (pin "3") (pinfunction "3_3") (pintype "passive"))
      (node (ref "K1") (pin "1") (pinfunction "O_1") (pintype "passive"))
      (node (ref "VO") (pin "1") (pinfunction "P_1") (pintype "passive"))
    )
    (net (code "67") (name "unconnected-(IC101A-2Y-Pad9)") (class "Default")
      (node (ref "IC101") (pin "9") (pinfunction "2Y_9") (pintype "output"))
    )
    (net (code "68") (name "unconnected-(IC103-RO-Pad1)") (class "Default")
      (node (ref "IC103") (pin "1") (pinfunction "RO_1") (pintype "output"))
    )
    (net (code "69") (name "unconnected-(J20-Pad1)") (class "Default")
      (node (ref "J20") (pin "1") (pinfunction "1_1") (pintype "passive"))
    )
    (net (code "70") (name "unconnected-(J20-Pad2)") (class "Default")
      (node (ref "J20") (pin "2") (pinfunction "2_2") (pintype "passive"))
    )
    (net (code "71") (name "unconnected-(JP2-Pad3)") (class "Default")
      (node (ref "JP2") (pin "3") (pinfunction "3_3") (pintype "passive"))
    )
    (net (code "72") (name "unconnected-(MC1-NC-PadP$24)") (class "Default")
      (node (ref "MC1") (pin "P$24") (pinfunction "NC_P$24") (pintype "bidirectional"))
    )
    (net (code "73") (name "unconnected-(MC1-NC-PadP$25)") (class "Default")
      (node (ref "MC1") (pin "P$25") (pinfunction "NC_P$25") (pintype "bidirectional"))
    )
    (net (code "74") (name "unconnected-(MC1-SS-PadP$16)") (class "Default")
      (node (ref "MC1") (pin "P$16") (pinfunction "SS_P$16") (pintype "bidirectional"))
    )
  )
)
